# Bottom_Board_V1.net
KiCad netlist of a schematic drawn in Altium Designer
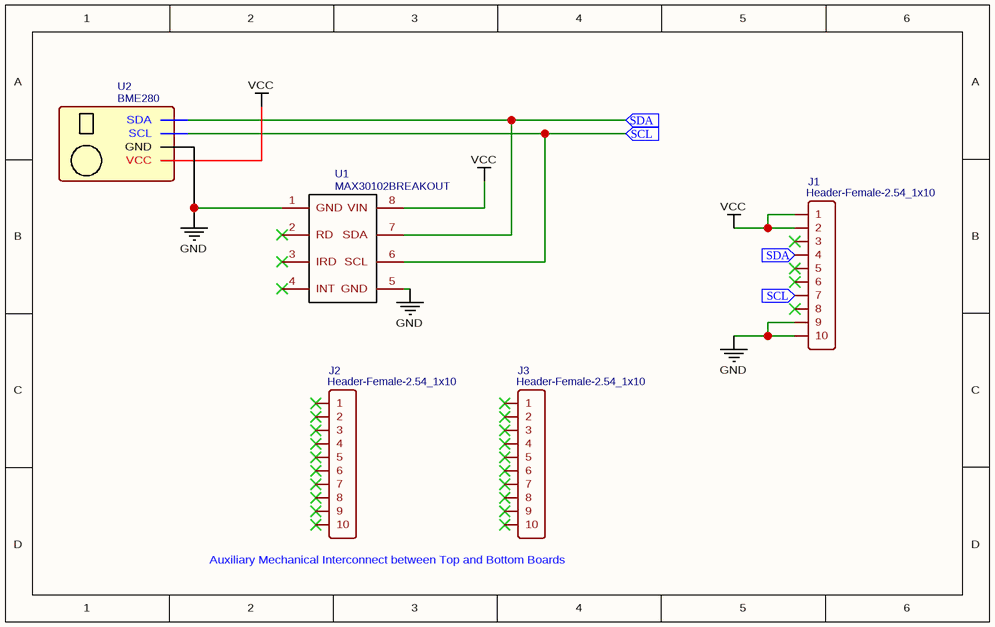
[diagram p0: Bottom+Board_V1.schdoc]

(export (version "E")
  (design (tool "Eeschema 10.0.6"))
  (components
    (comp (ref "J1")
      (value "Header-Female-2.54_1x10")
      (fields
        (field (name "BOM_MANUFACTURER PART") "2.54mm 1*10P Straight Female header Gold-plated")
        (field (name "BOM_SUPPLIER PART") "C35445")
      )
      (libsource (lib "altium-import") (part "root_0_Header-Female-2.54_1x10_"))
    )
    (comp (ref "J2")
      (value "Header-Female-2.54_1x10")
      (fields
        (field (name "BOM_MANUFACTURER PART") "2.54mm 1*10P Straight Female header Gold-plated")
        (field (name "BOM_SUPPLIER PART") "C35445")
      )
      (libsource (lib "altium-import") (part "root_0_Header-Female-2.54_1x10_"))
    )
    (comp (ref "J3")
      (value "Header-Female-2.54_1x10")
      (fields
        (field (name "BOM_MANUFACTURER PART") "2.54mm 1*10P Straight Female header Gold-plated")
        (field (name "BOM_SUPPLIER PART") "C35445")
      )
      (libsource (lib "altium-import") (part "root_0_Header-Female-2.54_1x10_"))
    )
    (comp (ref "U1")
      (value "MAX30102BREAKOUT")
      (fields (field (name "BOM_MANUFACTURER PART") "MAX30102") (field (name "CONTRIBUTOR") "nickklein95"))
      (libsource (lib "altium-import") (part "root_0_MAX30102BREAKOUT_"))
    )
    (comp (ref "U2")
      (value "BME280")
      (fields (field (name "CONTRIBUTOR") "Даниил Баюков (sleepsemek)"))
      (libsource (lib "altium-import") (part "root_2_BME280_"))
    )
  )
  (nets
    (net (code "1") (name "/SCL") (class "Default")
      (node (ref "J1") (pin "7") (pinfunction "7_7") (pintype "passive"))
      (node (ref "U1") (pin "6") (pinfunction "SCL_6") (pintype "passive"))
      (node (ref "U2") (pin "3") (pinfunction "SCL_3") (pintype "passive"))
    )
    (net (code "2") (name "/SDA") (class "Default")
      (node (ref "J1") (pin "4") (pinfunction "4_4") (pintype "passive"))
      (node (ref "U1") (pin "7") (pinfunction "SDA_7") (pintype "passive"))
      (node (ref "U2") (pin "4") (pinfunction "SDA_4") (pintype "passive"))
    )
    (net (code "3") (name "GND") (class "Default")
      (node (ref "J1") (pin "10") (pinfunction "10_10") (pintype "passive"))
      (node (ref "J1") (pin "9") (pinfunction "9_9") (pintype "passive"))
      (node (ref "U1") (pin "1") (pinfunction "GND_1") (pintype "passive"))
      (node (ref "U1") (pin "5") (pinfunction "GND_5") (pintype "passive"))
      (node (ref "U2") (pin "2") (pinfunction "GND_2") (pintype "passive"))
    )
    (net (code "4") (name "VCC") (class "Default")
      (node (ref "J1") (pin "1") (pinfunction "1_1") (pintype "passive"))
      (node (ref "J1") (pin "2") (pinfunction "2_2") (pintype "passive"))
      (node (ref "U1") (pin "8") (pinfunction "VIN_8") (pintype "passive"))
      (node (ref "U2") (pin "1") (pinfunction "VCC_1") (pintype "passive"))
    )
    (net (code "5") (name "unconnected-(J1-Pad3)") (class "Default")
      (node (ref "J1") (pin "3") (pinfunction "3_3") (pintype "passive+no_connect"))
    )
    (net (code "6") (name "unconnected-(J1-Pad5)") (class "Default")
      (node (ref "J1") (pin "5") (pinfunction "5_5") (pintype "passive+no_connect"))
    )
    (net (code "7") (name "unconnected-(J1-Pad6)") (class "Default")
      (node (ref "J1") (pin "6") (pinfunction "6_6") (pintype "passive+no_connect"))
    )
    (net (code "8") (name "unconnected-(J1-Pad8)") (class "Default")
      (node (ref "J1") (pin "8") (pinfunction "8_8") (pintype "passive+no_connect"))
    )
    (net (code "9") (name "unconnected-(J2-Pad1)") (class "Default")
      (node (ref "J2") (pin "1") (pinfunction "1_1") (pintype "passive+no_connect"))
    )
    (net (code "10") (name "unconnected-(J2-Pad2)") (class "Default")
      (node (ref "J2") (pin "2") (pinfunction "2_2") (pintype "passive+no_connect"))
    )
    (net (code "11") (name "unconnected-(J2-Pad3)") (class "Default")
      (node (ref "J2") (pin "3") (pinfunction "3_3") (pintype "passive+no_connect"))
    )
    (net (code "12") (name "unconnected-(J2-Pad4)") (class "Default")
      (node (ref "J2") (pin "4") (pinfunction "4_4") (pintype "passive+no_connect"))
    )
    (net (code "13") (name "unconnected-(J2-Pad5)") (class "Default")
      (node (ref "J2") (pin "5") (pinfunction "5_5") (pintype "passive+no_connect"))
    )
    (net (code "14") (name "unconnected-(J2-Pad6)") (class "Default")
      (node (ref "J2") (pin "6") (pinfunction "6_6") (pintype "passive+no_connect"))
    )
    (net (code "15") (name "unconnected-(J2-Pad7)") (class "Default")
      (node (ref "J2") (pin "7") (pinfunction "7_7") (pintype "passive+no_connect"))
    )
    (net (code "16") (name "unconnected-(J2-Pad8)") (class "Default")
      (node (ref "J2") (pin "8") (pinfunction "8_8") (pintype "passive+no_connect"))
    )
    (net (code "17") (name "unconnected-(J2-Pad9)") (class "Default")
      (node (ref "J2") (pin "9") (pinfunction "9_9") (pintype "passive+no_connect"))
    )
    (net (code "18") (name "unconnected-(J2-Pad10)") (class "Default")
      (node (ref "J2") (pin "10") (pinfunction "10_10") (pintype "passive+no_connect"))
    )
    (net (code "19") (name "unconnected-(J3-Pad1)") (class "Default")
      (node (ref "J3") (pin "1") (pinfunction "1_1") (pintype "passive+no_connect"))
    )
    (net (code "20") (name "unconnected-(J3-Pad2)") (class "Default")
      (node (ref "J3") (pin "2") (pinfunction "2_2") (pintype "passive+no_connect"))
    )
    (net (code "21") (name "unconnected-(J3-Pad3)") (class "Default")
      (node (ref "J3") (pin "3") (pinfunction "3_3") (pintype "passive+no_connect"))
    )
    (net (code "22") (name "unconnected-(J3-Pad4)") (class "Default")
      (node (ref "J3") (pin "4") (pinfunction "4_4") (pintype "passive+no_connect"))
    )
    (net (code "23") (name "unconnected-(J3-Pad5)") (class "Default")
      (node (ref "J3") (pin "5") (pinfunction "5_5") (pintype "passive+no_connect"))
    )
    (net (code "24") (name "unconnected-(J3-Pad6)") (class "Default")
      (node (ref "J3") (pin "6") (pinfunction "6_6") (pintype "passive+no_connect"))
    )
    (net (code "25") (name "unconnected-(J3-Pad7)") (class "Default")
      (node (ref "J3") (pin "7") (pinfunction "7_7") (pintype "passive+no_connect"))
    )
    (net (code "26") (name "unconnected-(J3-Pad8)") (class "Default")
      (node (ref "J3") (pin "8") (pinfunction "8_8") (pintype "passive+no_connect"))
    )
    (net (code "27") (name "unconnected-(J3-Pad9)") (class "Default")
      (node (ref "J3") (pin "9") (pinfunction "9_9") (pintype "passive+no_connect"))
    )
    (net (code "28") (name "unconnected-(J3-Pad10)") (class "Default")
      (node (ref "J3") (pin "10") (pinfunction "10_10") (pintype "passive+no_connect"))
    )
    (net (code "29") (name "unconnected-(U1-INT-Pad4)") (class "Default")
      (node (ref "U1") (pin "4") (pinfunction "INT_4") (pintype "passive+no_connect"))
    )
    (net (code "30") (name "unconnected-(U1-IRD-Pad3)") (class "Default")
      (node (ref "U1") (pin "3") (pinfunction "IRD_3") (pintype "passive+no_connect"))
    )
    (net (code "31") (name "unconnected-(U1-RD-Pad2)") (class "Default")
      (node (ref "U1") (pin "2") (pinfunction "RD_2") (pintype "passive+no_connect"))
    )
  )
)
